# EEG-RM_040218P03.net
KiCad netlist of a schematic drawn in EAGLE
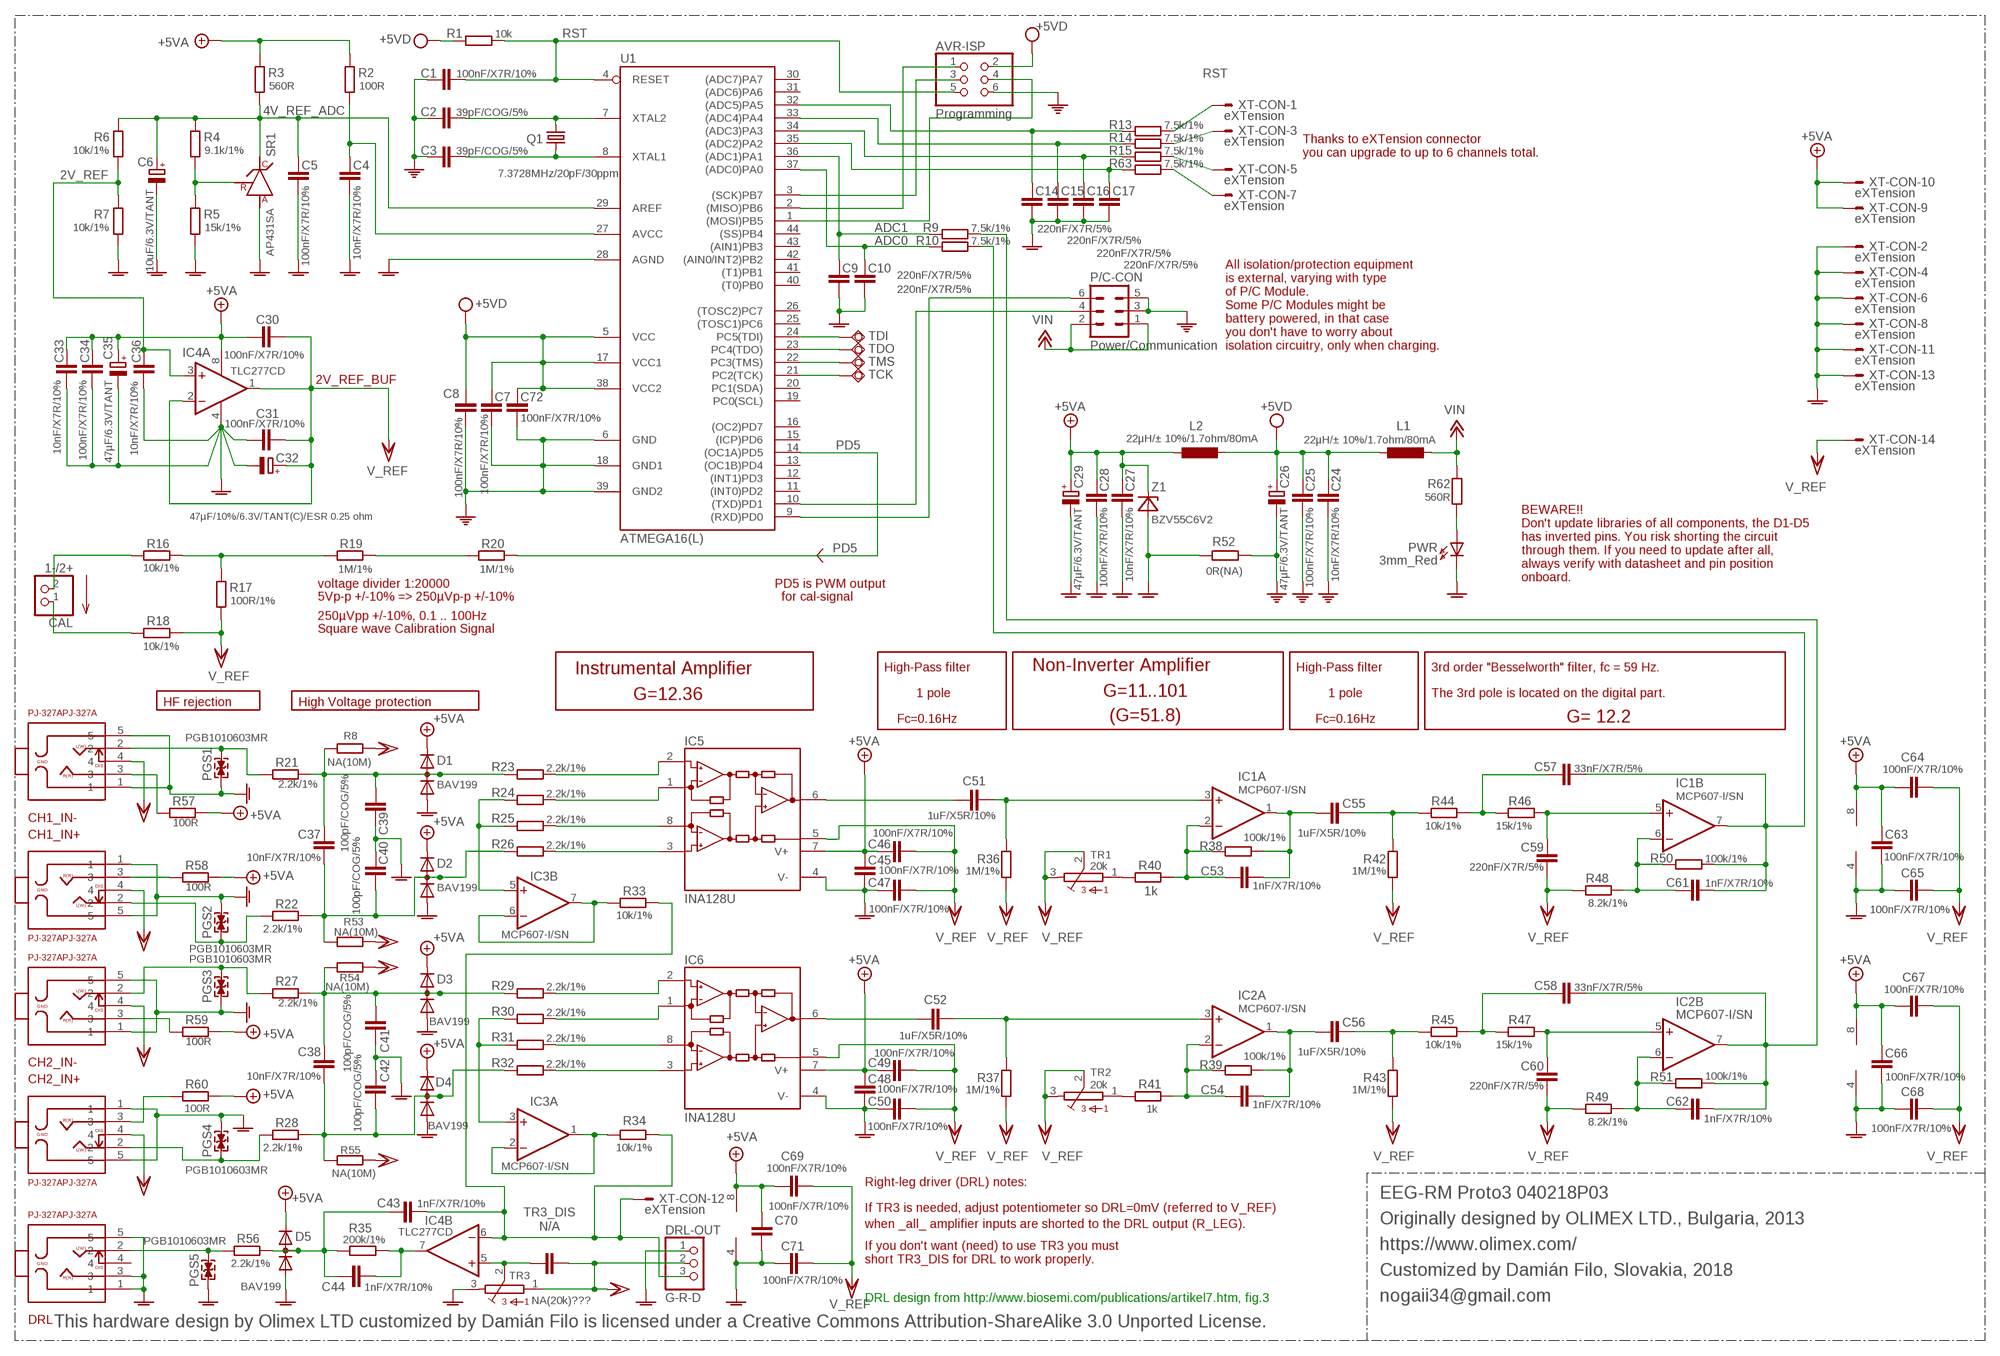
[diagram p0: schematic, sheet 1]

(export (version "E")
  (design (tool "Eeschema 10.0.6"))
  (components
    (comp (ref "AVR-ISP")
      (value "Programming")
      (footprint "eagle-import:2X03")
      (libsource (lib "eagle-import") (part "PINHD-2X3"))
    )
    (comp (ref "C1")
      (value "100nF/X7R/10%")
      (footprint "eagle-import:C0603")
      (libsource (lib "eagle-import") (part "C-EUC0603"))
    )
    (comp (ref "C2")
      (value "39pF/COG/5%")
      (footprint "eagle-import:C0603")
      (libsource (lib "eagle-import") (part "C-EUC0603"))
    )
    (comp (ref "C3")
      (value "39pF/COG/5%")
      (footprint "eagle-import:C0603")
      (libsource (lib "eagle-import") (part "C-EUC0603"))
    )
    (comp (ref "C4")
      (value "10nF/X7R/10%")
      (footprint "eagle-import:C0603")
      (libsource (lib "eagle-import") (part "C-EUC0603"))
    )
    (comp (ref "C5")
      (value "100nF/X7R/10%")
      (footprint "eagle-import:C0603")
      (libsource (lib "eagle-import") (part "C-EUC0603"))
    )
    (comp (ref "C6")
      (value "10uF/6.3V/TANT")
      (footprint "eagle-import:CT3216")
      (libsource (lib "eagle-import") (part "CPOL-EUCT3216"))
    )
    (comp (ref "C7")
      (value "100nF/X7R/10%")
      (footprint "eagle-import:C0603")
      (libsource (lib "eagle-import") (part "C-EUC0603"))
    )
    (comp (ref "C8")
      (value "100nF/X7R/10%")
      (footprint "eagle-import:C0603")
      (libsource (lib "eagle-import") (part "C-EUC0603"))
    )
    (comp (ref "C9")
      (value "220nF/X7R/5%")
      (footprint "eagle-import:C0603")
      (libsource (lib "eagle-import") (part "C-EUC0603"))
    )
    (comp (ref "C10")
      (value "220nF/X7R/5%")
      (footprint "eagle-import:C0603")
      (libsource (lib "eagle-import") (part "C-EUC0603"))
    )
    (comp (ref "C14")
      (value "220nF/X7R/5%")
      (footprint "eagle-import:C0603")
      (libsource (lib "eagle-import") (part "C-EUC0603"))
    )
    (comp (ref "C15")
      (value "220nF/X7R/5%")
      (footprint "eagle-import:C0603")
      (libsource (lib "eagle-import") (part "C-EUC0603"))
    )
    (comp (ref "C16")
      (value "220nF/X7R/5%")
      (footprint "eagle-import:C0603")
      (libsource (lib "eagle-import") (part "C-EUC0603"))
    )
    (comp (ref "C17")
      (value "220nF/X7R/5%")
      (footprint "eagle-import:C0603")
      (libsource (lib "eagle-import") (part "C-EUC0603"))
    )
    (comp (ref "C24")
      (value "10nF/X7R/10%")
      (footprint "eagle-import:C0603")
      (libsource (lib "eagle-import") (part "C-EUC0603"))
    )
    (comp (ref "C25")
      (value "100nF/X7R/10%")
      (footprint "eagle-import:C0603")
      (libsource (lib "eagle-import") (part "C-EUC0603"))
    )
    (comp (ref "C26")
      (value "47µF/6.3V/TANT")
      (footprint "eagle-import:CT3216")
      (libsource (lib "eagle-import") (part "CPOL-EUCT3216"))
    )
    (comp (ref "C27")
      (value "10nF/X7R/10%")
      (footprint "eagle-import:C0603")
      (libsource (lib "eagle-import") (part "C-EUC0603"))
    )
    (comp (ref "C28")
      (value "100nF/X7R/10%")
      (footprint "eagle-import:C0603")
      (libsource (lib "eagle-import") (part "C-EUC0603"))
    )
    (comp (ref "C29")
      (value "47µF/6.3V/TANT")
      (footprint "eagle-import:CT3216")
      (libsource (lib "eagle-import") (part "CPOL-EUCT3216"))
    )
    (comp (ref "C30")
      (value "100nF/X7R/10%")
      (footprint "eagle-import:C0603")
      (libsource (lib "eagle-import") (part "C-EUC0603"))
    )
    (comp (ref "C31")
      (value "100nF/X7R/10%")
      (footprint "eagle-import:C0603")
      (libsource (lib "eagle-import") (part "C-EUC0603"))
    )
    (comp (ref "C32")
      (value "47µF/10%/6.3V/TANT(C)/ESR 0.25 ohm")
      (footprint "eagle-import:CT3528")
      (libsource (lib "eagle-import") (part "CPOL-EUCT3528"))
    )
    (comp (ref "C33")
      (value "10nF/X7R/10%")
      (footprint "eagle-import:C0603")
      (libsource (lib "eagle-import") (part "C-EUC0603"))
    )
    (comp (ref "C34")
      (value "100nF/X7R/10%")
      (footprint "eagle-import:C0603")
      (libsource (lib "eagle-import") (part "C-EUC0603"))
    )
    (comp (ref "C35")
      (value "47µF/6.3V/TANT")
      (footprint "eagle-import:CT3216")
      (libsource (lib "eagle-import") (part "CPOL-EUCT3216"))
    )
    (comp (ref "C36")
      (value "10nF/X7R/10%")
      (footprint "eagle-import:C0603")
      (libsource (lib "eagle-import") (part "C-EUC0603"))
    )
    (comp (ref "C37")
      (value "10nF/X7R/10%")
      (footprint "eagle-import:C0603")
      (libsource (lib "eagle-import") (part "C-EUC0603"))
    )
    (comp (ref "C38")
      (value "10nF/X7R/10%")
      (footprint "eagle-import:C0603")
      (libsource (lib "eagle-import") (part "C-EUC0603"))
    )
    (comp (ref "C39")
      (value "100pF/COG/5%")
      (footprint "eagle-import:C0603")
      (libsource (lib "eagle-import") (part "C-EUC0603"))
    )
    (comp (ref "C40")
      (value "100pF/COG/5%")
      (footprint "eagle-import:C0603")
      (libsource (lib "eagle-import") (part "C-EUC0603"))
    )
    (comp (ref "C41")
      (value "100pF/COG/5%")
      (footprint "eagle-import:C0603")
      (libsource (lib "eagle-import") (part "C-EUC0603"))
    )
    (comp (ref "C42")
      (value "100pF/COG/5%")
      (footprint "eagle-import:C0603")
      (libsource (lib "eagle-import") (part "C-EUC0603"))
    )
    (comp (ref "C43")
      (value "1nF/X7R/10%")
      (footprint "eagle-import:C0603")
      (libsource (lib "eagle-import") (part "C-EUC0603"))
    )
    (comp (ref "C44")
      (value "1nF/X7R/10%")
      (footprint "eagle-import:C0603")
      (libsource (lib "eagle-import") (part "C-EUC0603"))
    )
    (comp (ref "C45")
      (value "100nF/X7R/10%")
      (footprint "eagle-import:C0603")
      (libsource (lib "eagle-import") (part "C-EUC0603"))
    )
    (comp (ref "C46")
      (value "100nF/X7R/10%")
      (footprint "eagle-import:C0603")
      (libsource (lib "eagle-import") (part "C-EUC0603"))
    )
    (comp (ref "C47")
      (value "100nF/X7R/10%")
      (footprint "eagle-import:C0603")
      (libsource (lib "eagle-import") (part "C-EUC0603"))
    )
    (comp (ref "C48")
      (value "100nF/X7R/10%")
      (footprint "eagle-import:C0603")
      (libsource (lib "eagle-import") (part "C-EUC0603"))
    )
    (comp (ref "C49")
      (value "100nF/X7R/10%")
      (footprint "eagle-import:C0603")
      (libsource (lib "eagle-import") (part "C-EUC0603"))
    )
    (comp (ref "C50")
      (value "100nF/X7R/10%")
      (footprint "eagle-import:C0603")
      (libsource (lib "eagle-import") (part "C-EUC0603"))
    )
    (comp (ref "C51")
      (value "1uF/X5R/10%")
      (footprint "eagle-import:C0603")
      (libsource (lib "eagle-import") (part "C-EUC0603"))
    )
    (comp (ref "C52")
      (value "1uF/X5R/10%")
      (footprint "eagle-import:C0603")
      (libsource (lib "eagle-import") (part "C-EUC0603"))
    )
    (comp (ref "C53")
      (value "1nF/X7R/10%")
      (footprint "eagle-import:C0603")
      (libsource (lib "eagle-import") (part "C-EUC0603"))
    )
    (comp (ref "C54")
      (value "1nF/X7R/10%")
      (footprint "eagle-import:C0603")
      (libsource (lib "eagle-import") (part "C-EUC0603"))
    )
    (comp (ref "C55")
      (value "1uF/X5R/10%")
      (footprint "eagle-import:C0603")
      (libsource (lib "eagle-import") (part "C-EUC0603"))
    )
    (comp (ref "C56")
      (value "1uF/X5R/10%")
      (footprint "eagle-import:C0603")
      (libsource (lib "eagle-import") (part "C-EUC0603"))
    )
    (comp (ref "C57")
      (value "33nF/X7R/5%")
      (footprint "eagle-import:C0603")
      (libsource (lib "eagle-import") (part "C-EUC0603"))
    )
    (comp (ref "C58")
      (value "33nF/X7R/5%")
      (footprint "eagle-import:C0603")
      (libsource (lib "eagle-import") (part "C-EUC0603"))
    )
    (comp (ref "C59")
      (value "220nF/X7R/5%")
      (footprint "eagle-import:C0603")
      (libsource (lib "eagle-import") (part "C-EUC0603"))
    )
    (comp (ref "C60")
      (value "220nF/X7R/5%")
      (footprint "eagle-import:C0603")
      (libsource (lib "eagle-import") (part "C-EUC0603"))
    )
    (comp (ref "C61")
      (value "1nF/X7R/10%")
      (footprint "eagle-import:C0603")
      (libsource (lib "eagle-import") (part "C-EUC0603"))
    )
    (comp (ref "C62")
      (value "1nF/X7R/10%")
      (footprint "eagle-import:C0603")
      (libsource (lib "eagle-import") (part "C-EUC0603"))
    )
    (comp (ref "C63")
      (value "100nF/X7R/10%")
      (footprint "eagle-import:C0603")
      (libsource (lib "eagle-import") (part "C-EUC0603"))
    )
    (comp (ref "C64")
      (value "100nF/X7R/10%")
      (footprint "eagle-import:C0603")
      (libsource (lib "eagle-import") (part "C-EUC0603"))
    )
    (comp (ref "C65")
      (value "100nF/X7R/10%")
      (footprint "eagle-import:C0603")
      (libsource (lib "eagle-import") (part "C-EUC0603"))
    )
    (comp (ref "C66")
      (value "100nF/X7R/10%")
      (footprint "eagle-import:C0603")
      (libsource (lib "eagle-import") (part "C-EUC0603"))
    )
    (comp (ref "C67")
      (value "100nF/X7R/10%")
      (footprint "eagle-import:C0603")
      (libsource (lib "eagle-import") (part "C-EUC0603"))
    )
    (comp (ref "C68")
      (value "100nF/X7R/10%")
      (footprint "eagle-import:C0603")
      (libsource (lib "eagle-import") (part "C-EUC0603"))
    )
    (comp (ref "C69")
      (value "100nF/X7R/10%")
      (footprint "eagle-import:C0603")
      (libsource (lib "eagle-import") (part "C-EUC0603"))
    )
    (comp (ref "C70")
      (value "100nF/X7R/10%")
      (footprint "eagle-import:C0603")
      (libsource (lib "eagle-import") (part "C-EUC0603"))
    )
    (comp (ref "C71")
      (value "100nF/X7R/10%")
      (footprint "eagle-import:C0603")
      (libsource (lib "eagle-import") (part "C-EUC0603"))
    )
    (comp (ref "C72")
      (value "100nF/X7R/10%")
      (footprint "eagle-import:C0603")
      (libsource (lib "eagle-import") (part "C-EUC0603"))
    )
    (comp (ref "CAL")
      (value "1-/2+")
      (footprint "eagle-import:1X02")
      (libsource (lib "eagle-import") (part "PINHD-1X2"))
    )
    (comp (ref "CH1_IN+")
      (value "PJ-327APJ-327A")
      (footprint "eagle-import:PJ-327A")
      (libsource (lib "eagle-import") (part "PJ-327APJ-327A"))
    )
    (comp (ref "CH1_IN-")
      (value "PJ-327APJ-327A")
      (footprint "eagle-import:PJ-327A")
      (libsource (lib "eagle-import") (part "PJ-327APJ-327A"))
    )
    (comp (ref "CH2_IN+")
      (value "PJ-327APJ-327A")
      (footprint "eagle-import:PJ-327A")
      (libsource (lib "eagle-import") (part "PJ-327APJ-327A"))
    )
    (comp (ref "CH2_IN-")
      (value "PJ-327APJ-327A")
      (footprint "eagle-import:PJ-327A")
      (libsource (lib "eagle-import") (part "PJ-327APJ-327A"))
    )
    (comp (ref "D1")
      (value "BAV199")
      (footprint "eagle-import:SOT23C")
      (libsource (lib "eagle-import") (part "DIODE_AC-AC__"))
    )
    (comp (ref "D2")
      (value "BAV199")
      (footprint "eagle-import:SOT23C")
      (libsource (lib "eagle-import") (part "DIODE_AC-AC__"))
    )
    (comp (ref "D3")
      (value "BAV199")
      (footprint "eagle-import:SOT23C")
      (libsource (lib "eagle-import") (part "DIODE_AC-AC__"))
    )
    (comp (ref "D4")
      (value "BAV199")
      (footprint "eagle-import:SOT23C")
      (libsource (lib "eagle-import") (part "DIODE_AC-AC__"))
    )
    (comp (ref "D5")
      (value "BAV199")
      (footprint "eagle-import:SOT23C")
      (libsource (lib "eagle-import") (part "DIODE_AC-AC__"))
    )
    (comp (ref "DRL")
      (value "PJ-327APJ-327A")
      (footprint "eagle-import:PJ-327A")
      (libsource (lib "eagle-import") (part "PJ-327APJ-327A"))
    )
    (comp (ref "DRL-OUT")
      (value "G-R-D")
      (footprint "eagle-import:1X03")
      (libsource (lib "eagle-import") (part "PINHD-1X3"))
    )
    (comp (ref "IC1")
      (value "MCP607-I/SN")
      (footprint "eagle-import:SO08")
      (libsource (lib "eagle-import") (part "LM358D"))
    )
    (comp (ref "IC2")
      (value "MCP607-I/SN")
      (footprint "eagle-import:SO08")
      (libsource (lib "eagle-import") (part "LM358D"))
    )
    (comp (ref "IC3")
      (value "MCP607-I/SN")
      (footprint "eagle-import:SO08")
      (libsource (lib "eagle-import") (part "LM358D"))
    )
    (comp (ref "IC4")
      (value "TLC277CD")
      (footprint "eagle-import:SO08")
      (libsource (lib "eagle-import") (part "LM358D"))
    )
    (comp (ref "IC5")
      (value "INA128U")
      (footprint "eagle-import:SO08")
      (fields (field (name "MF") "TEXAS INSTRUMENTS"))
      (libsource (lib "eagle-import") (part "INA128U"))
    )
    (comp (ref "IC6")
      (value "INA128U")
      (footprint "eagle-import:SO08")
      (fields (field (name "MF") "TEXAS INSTRUMENTS"))
      (libsource (lib "eagle-import") (part "INA128U"))
    )
    (comp (ref "L1")
      (value "22µH/± 10%/1.7ohm/80mA")
      (footprint "eagle-import:L2012C")
      (libsource (lib "eagle-import") (part "L-EUL2012C"))
    )
    (comp (ref "L2")
      (value "22µH/± 10%/1.7ohm/80mA")
      (footprint "eagle-import:L2012C")
      (libsource (lib "eagle-import") (part "L-EUL2012C"))
    )
    (comp (ref "P/C-CON")
      (value "Power/Communication")
      (footprint "eagle-import:ML6L")
      (libsource (lib "eagle-import") (part "ML6L"))
    )
    (comp (ref "PGS1")
      (value "PGB1010603MR")
      (footprint "eagle-import:0603")
      (libsource (lib "eagle-import") (part "PGB1010603MR(F2594TR-ND)"))
    )
    (comp (ref "PGS2")
      (value "PGB1010603MR")
      (footprint "eagle-import:0603")
      (libsource (lib "eagle-import") (part "PGB1010603MR(F2594TR-ND)"))
    )
    (comp (ref "PGS3")
      (value "PGB1010603MR")
      (footprint "eagle-import:0603")
      (libsource (lib "eagle-import") (part "PGB1010603MR(F2594TR-ND)"))
    )
    (comp (ref "PGS4")
      (value "PGB1010603MR")
      (footprint "eagle-import:0603")
      (libsource (lib "eagle-import") (part "PGB1010603MR(F2594TR-ND)"))
    )
    (comp (ref "PGS5")
      (value "PGB1010603MR")
      (footprint "eagle-import:0603")
      (libsource (lib "eagle-import") (part "PGB1010603MR(F2594TR-ND)"))
    )
    (comp (ref "PWR")
      (value "3mm_Red")
      (footprint "eagle-import:LED-3.0MM")
      (libsource (lib "eagle-import") (part "LED3.0MM"))
    )
    (comp (ref "Q1")
      (value "7.3728MHz/20pF/30ppm")
      (footprint "eagle-import:HC49_SMD2_THIN")
      (libsource (lib "eagle-import") (part "HC49/S1"))
    )
    (comp (ref "R1")
      (value "10k")
      (footprint "eagle-import:R0603")
      (libsource (lib "eagle-import") (part "R-EU_R0603"))
    )
    (comp (ref "R2")
      (value "100R")
      (footprint "eagle-import:R0603")
      (libsource (lib "eagle-import") (part "R-EU_R0603"))
    )
    (comp (ref "R3")
      (value "560R")
      (footprint "eagle-import:R0603")
      (libsource (lib "eagle-import") (part "R-EU_R0603"))
    )
    (comp (ref "R4")
      (value "9.1k/1%")
      (footprint "eagle-import:R0603")
      (libsource (lib "eagle-import") (part "R-EU_R0603"))
    )
    (comp (ref "R5")
      (value "15k/1%")
      (footprint "eagle-import:R0603")
      (libsource (lib "eagle-import") (part "R-EU_R0603"))
    )
    (comp (ref "R6")
      (value "10k/1%")
      (footprint "eagle-import:R0603")
      (libsource (lib "eagle-import") (part "R-EU_R0603"))
    )
    (comp (ref "R7")
      (value "10k/1%")
      (footprint "eagle-import:R0603")
      (libsource (lib "eagle-import") (part "R-EU_R0603"))
    )
    (comp (ref "R8")
      (value "NA(10M)")
      (footprint "eagle-import:R0603")
      (libsource (lib "eagle-import") (part "R-EU_R0603"))
    )
    (comp (ref "R9")
      (value "7.5k/1%")
      (footprint "eagle-import:M2012")
      (libsource (lib "eagle-import") (part "R-EU_M2012"))
    )
    (comp (ref "R10")
      (value "7.5k/1%")
      (footprint "eagle-import:M2012")
      (libsource (lib "eagle-import") (part "R-EU_M2012"))
    )
    (comp (ref "R13")
      (value "7.5k/1%")
      (footprint "eagle-import:M2012")
      (libsource (lib "eagle-import") (part "R-EU_M2012"))
    )
    (comp (ref "R14")
      (value "7.5k/1%")
      (footprint "eagle-import:M2012")
      (libsource (lib "eagle-import") (part "R-EU_M2012"))
    )
    (comp (ref "R15")
      (value "7.5k/1%")
      (footprint "eagle-import:M2012")
      (libsource (lib "eagle-import") (part "R-EU_M2012"))
    )
    (comp (ref "R16")
      (value "10k/1%")
      (footprint "eagle-import:R0603")
      (libsource (lib "eagle-import") (part "R-EU_R0603"))
    )
    (comp (ref "R17")
      (value "100R/1%")
      (footprint "eagle-import:R0603")
      (libsource (lib "eagle-import") (part "R-EU_R0603"))
    )
    (comp (ref "R18")
      (value "10k/1%")
      (footprint "eagle-import:R0603")
      (libsource (lib "eagle-import") (part "R-EU_R0603"))
    )
    (comp (ref "R19")
      (value "1M/1%")
      (footprint "eagle-import:R0603")
      (libsource (lib "eagle-import") (part "R-EU_R0603"))
    )
    (comp (ref "R20")
      (value "1M/1%")
      (footprint "eagle-import:R0603")
      (libsource (lib "eagle-import") (part "R-EU_R0603"))
    )
    (comp (ref "R21")
      (value "2.2k/1%")
      (footprint "eagle-import:R0603")
      (libsource (lib "eagle-import") (part "R-EU_R0603"))
    )
    (comp (ref "R22")
      (value "2.2k/1%")
      (footprint "eagle-import:R0603")
      (libsource (lib "eagle-import") (part "R-EU_R0603"))
    )
    (comp (ref "R23")
      (value "2.2k/1%")
      (footprint "eagle-import:R0603")
      (libsource (lib "eagle-import") (part "R-EU_R0603"))
    )
    (comp (ref "R24")
      (value "2.2k/1%")
      (footprint "eagle-import:R0603")
      (libsource (lib "eagle-import") (part "R-EU_R0603"))
    )
    (comp (ref "R25")
      (value "2.2k/1%")
      (footprint "eagle-import:R0603")
      (libsource (lib "eagle-import") (part "R-EU_R0603"))
    )
    (comp (ref "R26")
      (value "2.2k/1%")
      (footprint "eagle-import:R0603")
      (libsource (lib "eagle-import") (part "R-EU_R0603"))
    )
    (comp (ref "R27")
      (value "2.2k/1%")
      (footprint "eagle-import:R0603")
      (libsource (lib "eagle-import") (part "R-EU_R0603"))
    )
    (comp (ref "R28")
      (value "2.2k/1%")
      (footprint "eagle-import:R0603")
      (libsource (lib "eagle-import") (part "R-EU_R0603"))
    )
    (comp (ref "R29")
      (value "2.2k/1%")
      (footprint "eagle-import:R0603")
      (libsource (lib "eagle-import") (part "R-EU_R0603"))
    )
    (comp (ref "R30")
      (value "2.2k/1%")
      (footprint "eagle-import:R0603")
      (libsource (lib "eagle-import") (part "R-EU_R0603"))
    )
    (comp (ref "R31")
      (value "2.2k/1%")
      (footprint "eagle-import:R0603")
      (libsource (lib "eagle-import") (part "R-EU_R0603"))
    )
    (comp (ref "R32")
      (value "2.2k/1%")
      (footprint "eagle-import:R0603")
      (libsource (lib "eagle-import") (part "R-EU_R0603"))
    )
    (comp (ref "R33")
      (value "10k/1%")
      (footprint "eagle-import:R0603")
      (libsource (lib "eagle-import") (part "R-EU_R0603"))
    )
    (comp (ref "R34")
      (value "10k/1%")
      (footprint "eagle-import:R0603")
      (libsource (lib "eagle-import") (part "R-EU_R0603"))
    )
    (comp (ref "R35")
      (value "200k/1%")
      (footprint "eagle-import:R0603")
      (libsource (lib "eagle-import") (part "R-EU_R0603"))
    )
    (comp (ref "R36")
      (value "1M/1%")
      (footprint "eagle-import:R0603")
      (libsource (lib "eagle-import") (part "R-EU_R0603"))
    )
    (comp (ref "R37")
      (value "1M/1%")
      (footprint "eagle-import:R0603")
      (libsource (lib "eagle-import") (part "R-EU_R0603"))
    )
    (comp (ref "R38")
      (value "100k/1%")
      (footprint "eagle-import:R0603")
      (libsource (lib "eagle-import") (part "R-EU_R0603"))
    )
    (comp (ref "R39")
      (value "100k/1%")
      (footprint "eagle-import:R0603")
      (libsource (lib "eagle-import") (part "R-EU_R0603"))
    )
    (comp (ref "R40")
      (value "1k")
      (footprint "eagle-import:R0603")
      (libsource (lib "eagle-import") (part "R-EU_R0603"))
    )
    (comp (ref "R41")
      (value "1k")
      (footprint "eagle-import:R0603")
      (libsource (lib "eagle-import") (part "R-EU_R0603"))
    )
    (comp (ref "R42")
      (value "1M/1%")
      (footprint "eagle-import:R0603")
      (libsource (lib "eagle-import") (part "R-EU_R0603"))
    )
    (comp (ref "R43")
      (value "1M/1%")
      (footprint "eagle-import:R0603")
      (libsource (lib "eagle-import") (part "R-EU_R0603"))
    )
    (comp (ref "R44")
      (value "10k/1%")
      (footprint "eagle-import:R0603")
      (libsource (lib "eagle-import") (part "R-EU_R0603"))
    )
    (comp (ref "R45")
      (value "10k/1%")
      (footprint "eagle-import:R0603")
      (libsource (lib "eagle-import") (part "R-EU_R0603"))
    )
    (comp (ref "R46")
      (value "15k/1%")
      (footprint "eagle-import:R0603")
      (libsource (lib "eagle-import") (part "R-EU_R0603"))
    )
    (comp (ref "R47")
      (value "15k/1%")
      (footprint "eagle-import:R0603")
      (libsource (lib "eagle-import") (part "R-EU_R0603"))
    )
    (comp (ref "R48")
      (value "8.2k/1%")
      (footprint "eagle-import:R0603")
      (libsource (lib "eagle-import") (part "R-EU_R0603"))
    )
    (comp (ref "R49")
      (value "8.2k/1%")
      (footprint "eagle-import:R0603")
      (libsource (lib "eagle-import") (part "R-EU_R0603"))
    )
    (comp (ref "R50")
      (value "100k/1%")
      (footprint "eagle-import:R0603")
      (libsource (lib "eagle-import") (part "R-EU_R0603"))
    )
    (comp (ref "R51")
      (value "100k/1%")
      (footprint "eagle-import:R0603")
      (libsource (lib "eagle-import") (part "R-EU_R0603"))
    )
    (comp (ref "R52")
      (value "0R(NA)")
      (footprint "eagle-import:R0603")
      (libsource (lib "eagle-import") (part "R-EU_R0603"))
    )
    (comp (ref "R53")
      (value "NA(10M)")
      (footprint "eagle-import:R0603")
      (libsource (lib "eagle-import") (part "R-EU_R0603"))
    )
    (comp (ref "R54")
      (value "NA(10M)")
      (footprint "eagle-import:R0603")
      (libsource (lib "eagle-import") (part "R-EU_R0603"))
    )
    (comp (ref "R55")
      (value "NA(10M)")
      (footprint "eagle-import:R0603")
      (libsource (lib "eagle-import") (part "R-EU_R0603"))
    )
    (comp (ref "R56")
      (value "2.2k/1%")
      (footprint "eagle-import:R0603")
      (libsource (lib "eagle-import") (part "R-EU_R0603"))
    )
    (comp (ref "R57")
      (value "100R")
      (footprint "eagle-import:R0603")
      (libsource (lib "eagle-import") (part "R-EU_R0603"))
    )
    (comp (ref "R58")
      (value "100R")
      (footprint "eagle-import:R0603")
      (libsource (lib "eagle-import") (part "R-EU_R0603"))
    )
    (comp (ref "R59")
      (value "100R")
      (footprint "eagle-import:R0603")
      (libsource (lib "eagle-import") (part "R-EU_R0603"))
    )
    (comp (ref "R60")
      (value "100R")
      (footprint "eagle-import:R0603")
      (libsource (lib "eagle-import") (part "R-EU_R0603"))
    )
    (comp (ref "R62")
      (value "560R")
      (footprint "eagle-import:R0603")
      (libsource (lib "eagle-import") (part "R-EU_R0603"))
    )
    (comp (ref "R63")
      (value "7.5k/1%")
      (footprint "eagle-import:M2012")
      (libsource (lib "eagle-import") (part "R-EU_M2012"))
    )
    (comp (ref "SR1")
      (value "AP431SA")
      (footprint "eagle-import:SOT-23")
      (libsource (lib "eagle-import") (part "TL431'''"))
    )
    (comp (ref "TCK")
      (value "TESTPAD80/30")
      (footprint "eagle-import:SMD80_30")
      (libsource (lib "eagle-import") (part "TESTPAD80/30"))
    )
    (comp (ref "TDI")
      (value "TESTPAD80/30")
      (footprint "eagle-import:SMD80_30")
      (libsource (lib "eagle-import") (part "TESTPAD80/30"))
    )
    (comp (ref "TDO")
      (value "TESTPAD80/30")
      (footprint "eagle-import:SMD80_30")
      (libsource (lib "eagle-import") (part "TESTPAD80/30"))
    )
    (comp (ref "TMS")
      (value "TESTPAD80/30")
      (footprint "eagle-import:SMD80_30")
      (libsource (lib "eagle-import") (part "TESTPAD80/30"))
    )
    (comp (ref "TR1")
      (value "20k")
      (footprint "eagle-import:S64Y")
      (libsource (lib "eagle-import") (part "S64Y"))
    )
    (comp (ref "TR2")
      (value "20k")
      (footprint "eagle-import:S64Y")
      (libsource (lib "eagle-import") (part "S64Y"))
    )
    (comp (ref "TR3")
      (value "NA(20k)???")
      (footprint "eagle-import:S64Y")
      (libsource (lib "eagle-import") (part "S64Y"))
    )
    (comp (ref "TR3_DIS")
      (value "N/A")
      (footprint "eagle-import:C0402")
      (libsource (lib "eagle-import") (part "C-EUC0402"))
    )
    (comp (ref "U1")
      (value "ATMEGA16(L)")
      (footprint "eagle-import:44TQFP")
      (libsource (lib "eagle-import") (part "ATMEGA16"))
    )
    (comp (ref "XT-CON")
      (value "eXTension")
      (footprint "eagle-import:ML14L")
      (libsource (lib "eagle-import") (part "ML14EL"))
    )
    (comp (ref "Z1")
      (value "BZV55C6V2")
      (footprint "eagle-import:MINI-MELF")
      (libsource (lib "eagle-import") (part "ZDIOD-SMD"))
    )
  )
  (nets
    (net (code "1") (name "+5VA") (class "Default")
      (node (ref "C27") (pin "1") (pinfunction "1_1") (pintype "passive"))
      (node (ref "C28") (pin "1") (pinfunction "1_1") (pintype "passive"))
      (node (ref "C29") (pin "+") (pinfunction "+_+") (pintype "passive"))
      (node (ref "C30") (pin "2") (pinfunction "2_2") (pintype "passive"))
      (node (ref "C33") (pin "1") (pinfunction "1_1") (pintype "passive"))
      (node (ref "C34") (pin "1") (pinfunction "1_1") (pintype "passive"))
      (node (ref "C35") (pin "+") (pinfunction "+_+") (pintype "passive"))
      (node (ref "C45") (pin "1") (pinfunction "1_1") (pintype "passive"))
      (node (ref "C46") (pin "1") (pinfunction "1_1") (pintype "passive"))
      (node (ref "C48") (pin "1") (pinfunction "1_1") (pintype "passive"))
      (node (ref "C49") (pin "1") (pinfunction "1_1") (pintype "passive"))
      (node (ref "C63") (pin "1") (pinfunction "1_1") (pintype "passive"))
      (node (ref "C64") (pin "1") (pinfunction "1_1") (pintype "passive"))
      (node (ref "C66") (pin "1") (pinfunction "1_1") (pintype "passive"))
      (node (ref "C67") (pin "1") (pinfunction "1_1") (pintype "passive"))
      (node (ref "C69") (pin "1") (pinfunction "1_1") (pintype "passive"))
      (node (ref "C70") (pin "1") (pinfunction "1_1") (pintype "passive"))
      (node (ref "D1") (pin "1") (pinfunction "K_1") (pintype "passive"))
      (node (ref "D2") (pin "1") (pinfunction "K_1") (pintype "passive"))
      (node (ref "D3") (pin "1") (pinfunction "K_1") (pintype "passive"))
      (node (ref "D4") (pin "1") (pinfunction "K_1") (pintype "passive"))
      (node (ref "D5") (pin "1") (pinfunction "K_1") (pintype "passive"))
      (node (ref "IC1") (pin "8") (pinfunction "V+_8") (pintype "power_in"))
      (node (ref "IC2") (pin "8") (pinfunction "V+_8") (pintype "power_in"))
      (node (ref "IC3") (pin "8") (pinfunction "V+_8") (pintype "power_in"))
      (node (ref "IC4") (pin "8") (pinfunction "V+_8") (pintype "power_in"))
      (node (ref "IC5") (pin "7") (pinfunction "V+_7") (pintype "power_in"))
      (node (ref "IC6") (pin "7") (pinfunction "V+_7") (pintype "power_in"))
      (node (ref "L2") (pin "2") (pinfunction "2_2") (pintype "passive"))
      (node (ref "R2") (pin "2") (pinfunction "2_2") (pintype "passive"))
      (node (ref "R3") (pin "2") (pinfunction "2_2") (pintype "passive"))
      (node (ref "R57") (pin "2") (pinfunction "2_2") (pintype "passive"))
      (node (ref "R58") (pin "2") (pinfunction "2_2") (pintype "passive"))
      (node (ref "R59") (pin "2") (pinfunction "2_2") (pintype "passive"))
      (node (ref "R60") (pin "2") (pinfunction "2_2") (pintype "passive"))
      (node (ref "XT-CON") (pin "10") (pinfunction "S_10") (pintype "passive"))
      (node (ref "XT-CON") (pin "9") (pinfunction "S_9") (pintype "passive"))
      (node (ref "Z1") (pin "1") (pinfunction "C_1") (pintype "passive"))
    )
    (net (code "2") (name "+5VD") (class "Default")
      (node (ref "AVR-ISP") (pin "2") (pinfunction "2_2") (pintype "passive"))
      (node (ref "C24") (pin "1") (pinfunction "1_1") (pintype "passive"))
      (node (ref "C25") (pin "1") (pinfunction "1_1") (pintype "passive"))
      (node (ref "C26") (pin "+") (pinfunction "+_+") (pintype "passive"))
      (node (ref "C7") (pin "1") (pinfunction "1_1") (pintype "passive"))
      (node (ref "C72") (pin "1") (pinfunction "1_1") (pintype "passive"))
      (node (ref "C8") (pin "1") (pinfunction "1_1") (pintype "passive"))
      (node (ref "L1") (pin "2") (pinfunction "2_2") (pintype "passive"))
      (node (ref "L2") (pin "1") (pinfunction "1_1") (pintype "passive"))
      (node (ref "R1") (pin "1") (pinfunction "1_1") (pintype "passive"))
      (node (ref "U1") (pin "17") (pinfunction "VCC1_17") (pintype "bidirectional"))
      (node (ref "U1") (pin "38") (pinfunction "VCC2_38") (pintype "bidirectional"))
      (node (ref "U1") (pin "5") (pinfunction "VCC_5") (pintype "power_in"))
    )
    (net (code "3") (name "/2V_REF") (class "Default")
      (node (ref "C36") (pin "1") (pinfunction "1_1") (pintype "passive"))
      (node (ref "IC4") (pin "3") (pinfunction "+IN_3") (pintype "input"))
      (node (ref "R6") (pin "1") (pinfunction "1_1") (pintype "passive"))
      (node (ref "R7") (pin "2") (pinfunction "2_2") (pintype "passive"))
    )
    (net (code "4") (name "/4V_REF_ADC") (class "Default")
      (node (ref "C5") (pin "1") (pinfunction "1_1") (pintype "passive"))
      (node (ref "C6") (pin "+") (pinfunction "+_+") (pintype "passive"))
      (node (ref "R3") (pin "1") (pinfunction "1_1") (pintype "passive"))
      (node (ref "R4") (pin "2") (pinfunction "2_2") (pintype "passive"))
      (node (ref "R6") (pin "2") (pinfunction "2_2") (pintype "passive"))
      (node (ref "SR1") (pin "1") (pinfunction "C_1") (pintype "input"))
      (node (ref "U1") (pin "29") (pinfunction "AREF_29") (pintype "power_in"))
    )
    (net (code "5") (name "/ADC0") (class "Default")
      (node (ref "C10") (pin "1") (pinfunction "1_1") (pintype "passive"))
      (node (ref "R10") (pin "1") (pinfunction "1_1") (pintype "passive"))
      (node (ref "U1") (pin "37") (pinfunction "(ADC0)PA0_37") (pintype "bidirectional"))
    )
    (net (code "6") (name "/ADC1") (class "Default")
      (node (ref "C9") (pin "1") (pinfunction "1_1") (pintype "passive"))
      (node (ref "R9") (pin "1") (pinfunction "1_1") (pintype "passive"))
      (node (ref "U1") (pin "36") (pinfunction "(ADC1)PA1_36") (pintype "bidirectional"))
    )
    (net (code "7") (name "/PD5") (class "Default")
      (node (ref "R20") (pin "2") (pinfunction "2_2") (pintype "passive"))
      (node (ref "U1") (pin "14") (pinfunction "(OC1A)PD5_14") (pintype "bidirectional"))
    )
    (net (code "8") (name "/RST") (class "Default")
      (node (ref "AVR-ISP") (pin "5") (pinfunction "5_5") (pintype "passive"))
      (node (ref "C1") (pin "1") (pinfunction "1_1") (pintype "passive"))
      (node (ref "R1") (pin "2") (pinfunction "2_2") (pintype "passive"))
      (node (ref "U1") (pin "4") (pinfunction "RESET_4") (pintype "input"))
    )
    (net (code "9") (name "GNDA") (class "Default")
      (node (ref "C10") (pin "2") (pinfunction "2_2") (pintype "passive"))
      (node (ref "C14") (pin "2") (pinfunction "2_2") (pintype "passive"))
      (node (ref "C15") (pin "2") (pinfunction "2_2") (pintype "passive"))
      (node (ref "C16") (pin "2") (pinfunction "2_2") (pintype "passive"))
      (node (ref "C17") (pin "2") (pinfunction "2_2") (pintype "passive"))
      (node (ref "C27") (pin "2") (pinfunction "2_2") (pintype "passive"))
      (node (ref "C28") (pin "2") (pinfunction "2_2") (pintype "passive"))
      (node (ref "C29") (pin "-") (pinfunction "-_-") (pintype "passive"))
      (node (ref "C31") (pin "2") (pinfunction "2_2") (pintype "passive"))
      (node (ref "C32") (pin "-") (pinfunction "-_-") (pintype "passive"))
      (node (ref "C33") (pin "2") (pinfunction "2_2") (pintype "passive"))
      (node (ref "C34") (pin "2") (pinfunction "2_2") (pintype "passive"))
      (node (ref "C35") (pin "-") (pinfunction "-_-") (pintype "passive"))
      (node (ref "C36") (pin "2") (pinfunction "2_2") (pintype "passive"))
      (node (ref "C39") (pin "1") (pinfunction "1_1") (pintype "passive"))
      (node (ref "C4") (pin "2") (pinfunction "2_2") (pintype "passive"))
      (node (ref "C40") (pin "2") (pinfunction "2_2") (pintype "passive"))
      (node (ref "C41") (pin "1") (pinfunction "1_1") (pintype "passive"))
      (node (ref "C42") (pin "2") (pinfunction "2_2") (pintype "passive"))
      (node (ref "C45") (pin "2") (pinfunction "2_2") (pintype "passive"))
      (node (ref "C47") (pin "1") (pinfunction "1_1") (pintype "passive"))
      (node (ref "C48") (pin "2") (pinfunction "2_2") (pintype "passive"))
      (node (ref "C5") (pin "2") (pinfunction "2_2") (pintype "passive"))
      (node (ref "C50") (pin "1") (pinfunction "1_1") (pintype "passive"))
      (node (ref "C6") (pin "-") (pinfunction "-_-") (pintype "passive"))
      (node (ref "C63") (pin "2") (pinfunction "2_2") (pintype "passive"))
      (node (ref "C65") (pin "1") (pinfunction "1_1") (pintype "passive"))
      (node (ref "C66") (pin "2") (pinfunction "2_2") (pintype "passive"))
      (node (ref "C68") (pin "1") (pinfunction "1_1") (pintype "passive"))
      (node (ref "C70") (pin "2") (pinfunction "2_2") (pintype "passive"))
      (node (ref "C71") (pin "1") (pinfunction "1_1") (pintype "passive"))
      (node (ref "C9") (pin "2") (pinfunction "2_2") (pintype "passive"))
      (node (ref "CH1_IN+") (pin "1") (pinfunction "1_1") (pintype "bidirectional"))
      (node (ref "CH1_IN+") (pin "5") (pinfunction "5_5") (pintype "bidirectional"))
      (node (ref "CH1_IN-") (pin "1") (pinfunction "1_1") (pintype "bidirectional"))
      (node (ref "CH1_IN-") (pin "5") (pinfunction "5_5") (pintype "bidirectional"))
      (node (ref "CH2_IN+") (pin "1") (pinfunction "1_1") (pintype "bidirectional"))
      (node (ref "CH2_IN+") (pin "5") (pinfunction "5_5") (pintype "bidirectional"))
      (node (ref "CH2_IN-") (pin "1") (pinfunction "1_1") (pintype "bidirectional"))
      (node (ref "CH2_IN-") (pin "5") (pinfunction "5_5") (pintype "bidirectional"))
      (node (ref "D1") (pin "2") (pinfunction "A_2") (pintype "passive"))
      (node (ref "D2") (pin "2") (pinfunction "A_2") (pintype "passive"))
      (node (ref "D3") (pin "2") (pinfunction "A_2") (pintype "passive"))
      (node (ref "D4") (pin "2") (pinfunction "A_2") (pintype "passive"))
      (node (ref "D5") (pin "2") (pinfunction "A_2") (pintype "passive"))
      (node (ref "DRL") (pin "1") (pinfunction "1_1") (pintype "bidirectional"))
      (node (ref "DRL") (pin "3") (pinfunction "3_3") (pintype "bidirectional"))
      (node (ref "DRL") (pin "5") (pinfunction "5_5") (pintype "bidirectional"))
      (node (ref "DRL-OUT") (pin "1") (pinfunction "1_1") (pintype "passive"))
      (node (ref "IC1") (pin "4") (pinfunction "V-_4") (pintype "power_in"))
      (node (ref "IC2") (pin "4") (pinfunction "V-_4") (pintype "power_in"))
      (node (ref "IC3") (pin "4") (pinfunction "V-_4") (pintype "power_in"))
      (node (ref "IC4") (pin "4") (pinfunction "V-_4") (pintype "power_in"))
      (node (ref "IC5") (pin "4") (pinfunction "V-_4") (pintype "power_in"))
      (node (ref "IC6") (pin "4") (pinfunction "V-_4") (pintype "power_in"))
      (node (ref "PGS1") (pin "1") (pinfunction "1_1") (pintype "input"))
      (node (ref "PGS2") (pin "2") (pinfunction "2_2") (pintype "input"))
      (node (ref "PGS3") (pin "1") (pinfunction "1_1") (pintype "input"))
      (node (ref "PGS4") (pin "2") (pinfunction "2_2") (pintype "input"))
      (node (ref "PGS5") (pin "1") (pinfunction "1_1") (pintype "input"))
      (node (ref "PWR") (pin "K") (pinfunction "C_K") (pintype "passive"))
      (node (ref "R5") (pin "1") (pinfunction "1_1") (pintype "passive"))
      (node (ref "R52") (pin "1") (pinfunction "1_1") (pintype "passive"))
      (node (ref "R7") (pin "1") (pinfunction "1_1") (pintype "passive"))
      (node (ref "SR1") (pin "3") (pinfunction "A_3") (pintype "input"))
      (node (ref "TR3") (pin "3") (pinfunction "3_3") (pintype "passive"))
      (node (ref "U1") (pin "28") (pinfunction "AGND_28") (pintype "power_in"))
      (node (ref "XT-CON") (pin "11") (pinfunction "S_11") (pintype "passive"))
      (node (ref "XT-CON") (pin "13") (pinfunction "S_13") (pintype "passive"))
      (node (ref "XT-CON") (pin "2") (pinfunction "S_2") (pintype "passive"))
      (node (ref "XT-CON") (pin "4") (pinfunction "S_4") (pintype "passive"))
      (node (ref "XT-CON") (pin "6") (pinfunction "S_6") (pintype "passive"))
      (node (ref "XT-CON") (pin "8") (pinfunction "S_8") (pintype "passive"))
      (node (ref "Z1") (pin "2") (pinfunction "A_2") (pintype "passive"))
    )
    (net (code "10") (name "Net-(C55-Pad2)") (class "Default")
      (node (ref "C55") (pin "2") (pinfunction "2_2") (pintype "passive"))
      (node (ref "R42") (pin "1") (pinfunction "1_1") (pintype "passive"))
      (node (ref "R44") (pin "1") (pinfunction "1_1") (pintype "passive"))
    )
    (net (code "11") (name "Net-(C56-Pad2)") (class "Default")
      (node (ref "C56") (pin "2") (pinfunction "2_2") (pintype "passive"))
      (node (ref "R43") (pin "1") (pinfunction "1_1") (pintype "passive"))
      (node (ref "R45") (pin "1") (pinfunction "1_1") (pintype "passive"))
    )
    (net (code "12") (name "Net-(C57-Pad1)") (class "Default")
      (node (ref "C57") (pin "1") (pinfunction "1_1") (pintype "passive"))
      (node (ref "R44") (pin "2") (pinfunction "2_2") (pintype "passive"))
      (node (ref "R46") (pin "1") (pinfunction "1_1") (pintype "passive"))
    )
    (net (code "13") (name "Net-(C58-Pad1)") (class "Default")
      (node (ref "C58") (pin "1") (pinfunction "1_1") (pintype "passive"))
      (node (ref "R45") (pin "2") (pinfunction "2_2") (pintype "passive"))
      (node (ref "R47") (pin "1") (pinfunction "1_1") (pintype "passive"))
    )
    (net (code "14") (name "Net-(CAL-Pad1)") (class "Default")
      (node (ref "CAL") (pin "1") (pinfunction "1_1") (pintype "passive"))
      (node (ref "R18") (pin "1") (pinfunction "1_1") (pintype "passive"))
    )
    (net (code "15") (name "Net-(CAL-Pad2)") (class "Default")
      (node (ref "CAL") (pin "2") (pinfunction "2_2") (pintype "passive"))
      (node (ref "R16") (pin "1") (pinfunction "1_1") (pintype "passive"))
    )
    (net (code "16") (name "Net-(CH1_IN+-Pad2)") (class "Default")
      (node (ref "CH1_IN+") (pin "2") (pinfunction "2_2") (pintype "bidirectional"))
      (node (ref "PGS2") (pin "1") (pinfunction "1_1") (pintype "input"))
      (node (ref "R22") (pin "1") (pinfunction "1_1") (pintype "passive"))
    )
    (net (code "17") (name "Net-(CH1_IN+-Pad3)") (class "Default")
      (node (ref "CH1_IN+") (pin "3") (pinfunction "3_3") (pintype "bidirectional"))
      (node (ref "R58") (pin "1") (pinfunction "1_1") (pintype "passive"))
    )
    (net (code "18") (name "Net-(CH1_IN--Pad2)") (class "Default")
      (node (ref "CH1_IN-") (pin "2") (pinfunction "2_2") (pintype "bidirectional"))
      (node (ref "PGS1") (pin "2") (pinfunction "2_2") (pintype "input"))
      (node (ref "R21") (pin "1") (pinfunction "1_1") (pintype "passive"))
    )
    (net (code "19") (name "Net-(CH1_IN--Pad3)") (class "Default")
      (node (ref "CH1_IN-") (pin "3") (pinfunction "3_3") (pintype "bidirectional"))
      (node (ref "R57") (pin "1") (pinfunction "1_1") (pintype "passive"))
    )
    (net (code "20") (name "Net-(CH2_IN+-Pad2)") (class "Default")
      (node (ref "CH2_IN+") (pin "2") (pinfunction "2_2") (pintype "bidirectional"))
      (node (ref "PGS4") (pin "1") (pinfunction "1_1") (pintype "input"))
      (node (ref "R28") (pin "1") (pinfunction "1_1") (pintype "passive"))
    )
    (net (code "21") (name "Net-(CH2_IN+-Pad3)") (class "Default")
      (node (ref "CH2_IN+") (pin "3") (pinfunction "3_3") (pintype "bidirectional"))
      (node (ref "R60") (pin "1") (pinfunction "1_1") (pintype "passive"))
    )
    (net (code "22") (name "Net-(CH2_IN--Pad2)") (class "Default")
      (node (ref "CH2_IN-") (pin "2") (pinfunction "2_2") (pintype "bidirectional"))
      (node (ref "PGS3") (pin "2") (pinfunction "2_2") (pintype "input"))
      (node (ref "R27") (pin "1") (pinfunction "1_1") (pintype "passive"))
    )
    (net (code "23") (name "Net-(CH2_IN--Pad3)") (class "Default")
      (node (ref "CH2_IN-") (pin "3") (pinfunction "3_3") (pintype "bidirectional"))
      (node (ref "R59") (pin "1") (pinfunction "1_1") (pintype "passive"))
    )
    (net (code "24") (name "Net-(D1-AK)") (class "Default")
      (node (ref "C37") (pin "2") (pinfunction "2_2") (pintype "passive"))
      (node (ref "C39") (pin "2") (pinfunction "2_2") (pintype "passive"))
      (node (ref "D1") (pin "3") (pinfunction "AK_3") (pintype "passive"))
      (node (ref "R21") (pin "2") (pinfunction "2_2") (pintype "passive"))
      (node (ref "R23") (pin "2") (pinfunction "2_2") (pintype "passive"))
      (node (ref "R8") (pin "2") (pinfunction "2_2") (pintype "passive"))
    )
    (net (code "25") (name "Net-(D2-AK)") (class "Default")
      (node (ref "C37") (pin "1") (pinfunction "1_1") (pintype "passive"))
      (node (ref "C40") (pin "1") (pinfunction "1_1") (pintype "passive"))
      (node (ref "D2") (pin "3") (pinfunction "AK_3") (pintype "passive"))
      (node (ref "R22") (pin "2") (pinfunction "2_2") (pintype "passive"))
      (node (ref "R26") (pin "2") (pinfunction "2_2") (pintype "passive"))
      (node (ref "R53") (pin "2") (pinfunction "2_2") (pintype "passive"))
    )
    (net (code "26") (name "Net-(D3-AK)") (class "Default")
      (node (ref "C38") (pin "2") (pinfunction "2_2") (pintype "passive"))
      (node (ref "C41") (pin "2") (pinfunction "2_2") (pintype "passive"))
      (node (ref "D3") (pin "3") (pinfunction "AK_3") (pintype "passive"))
      (node (ref "R27") (pin "2") (pinfunction "2_2") (pintype "passive"))
      (node (ref "R29") (pin "2") (pinfunction "2_2") (pintype "passive"))
      (node (ref "R54") (pin "2") (pinfunction "2_2") (pintype "passive"))
    )
    (net (code "27") (name "Net-(D4-AK)") (class "Default")
      (node (ref "C38") (pin "1") (pinfunction "1_1") (pintype "passive"))
      (node (ref "C42") (pin "1") (pinfunction "1_1") (pintype "passive"))
      (node (ref "D4") (pin "3") (pinfunction "AK_3") (pintype "passive"))
      (node (ref "R28") (pin "2") (pinfunction "2_2") (pintype "passive"))
      (node (ref "R32") (pin "2") (pinfunction "2_2") (pintype "passive"))
      (node (ref "R55") (pin "2") (pinfunction "2_2") (pintype "passive"))
    )
    (net (code "28") (name "Net-(D5-AK)") (class "Default")
      (node (ref "C43") (pin "2") (pinfunction "2_2") (pintype "passive"))
      (node (ref "C44") (pin "2") (pinfunction "2_2") (pintype "passive"))
      (node (ref "D5") (pin "3") (pinfunction "AK_3") (pintype "passive"))
      (node (ref "R35") (pin "1") (pinfunction "1_1") (pintype "passive"))
      (node (ref "R56") (pin "2") (pinfunction "2_2") (pintype "passive"))
    )
    (net (code "29") (name "Net-(DRL-Pad2)") (class "Default")
      (node (ref "DRL") (pin "2") (pinfunction "2_2") (pintype "bidirectional"))
      (node (ref "PGS5") (pin "2") (pinfunction "2_2") (pintype "input"))
      (node (ref "R56") (pin "1") (pinfunction "1_1") (pintype "passive"))
    )
    (net (code "30") (name "Net-(IC1A-+IN)") (class "Default")
      (node (ref "C51") (pin "2") (pinfunction "2_2") (pintype "passive"))
      (node (ref "IC1") (pin "3") (pinfunction "+IN_3") (pintype "input"))
      (node (ref "R36") (pin "1") (pinfunction "1_1") (pintype "passive"))
    )
    (net (code "31") (name "Net-(IC1A--IN)") (class "Default")
      (node (ref "C53") (pin "1") (pinfunction "1_1") (pintype "passive"))
      (node (ref "IC1") (pin "2") (pinfunction "-IN_2") (pintype "input"))
      (node (ref "R38") (pin "1") (pinfunction "1_1") (pintype "passive"))
      (node (ref "R40") (pin "1") (pinfunction "1_1") (pintype "passive"))
    )
    (net (code "32") (name "Net-(IC1A-OUT)") (class "Default")
      (node (ref "C53") (pin "2") (pinfunction "2_2") (pintype "passive"))
      (node (ref "C55") (pin "1") (pinfunction "1_1") (pintype "passive"))
      (node (ref "IC1") (pin "1") (pinfunction "OUT_1") (pintype "output"))
      (node (ref "R38") (pin "2") (pinfunction "2_2") (pintype "passive"))
    )
    (net (code "33") (name "Net-(IC1B-+IN)") (class "Default")
      (node (ref "C59") (pin "1") (pinfunction "1_1") (pintype "passive"))
      (node (ref "IC1") (pin "5") (pinfunction "+IN_5") (pintype "input"))
      (node (ref "R46") (pin "2") (pinfunction "2_2") (pintype "passive"))
    )
    (net (code "34") (name "Net-(IC1B--IN)") (class "Default")
      (node (ref "C61") (pin "1") (pinfunction "1_1") (pintype "passive"))
      (node (ref "IC1") (pin "6") (pinfunction "-IN_6") (pintype "input"))
      (node (ref "R48") (pin "1") (pinfunction "1_1") (pintype "passive"))
      (node (ref "R50") (pin "1") (pinfunction "1_1") (pintype "passive"))
    )
    (net (code "35") (name "Net-(IC1B-OUT)") (class "Default")
      (node (ref "C57") (pin "2") (pinfunction "2_2") (pintype "passive"))
      (node (ref "C61") (pin "2") (pinfunction "2_2") (pintype "passive"))
      (node (ref "IC1") (pin "7") (pinfunction "OUT_7") (pintype "output"))
      (node (ref "R10") (pin "2") (pinfunction "2_2") (pintype "passive"))
      (node (ref "R50") (pin "2") (pinfunction "2_2") (pintype "passive"))
    )
    (net (code "36") (name "Net-(IC2A-+IN)") (class "Default")
      (node (ref "C52") (pin "2") (pinfunction "2_2") (pintype "passive"))
      (node (ref "IC2") (pin "3") (pinfunction "+IN_3") (pintype "input"))
      (node (ref "R37") (pin "1") (pinfunction "1_1") (pintype "passive"))
    )
    (net (code "37") (name "Net-(IC2A--IN)") (class "Default")
      (node (ref "C54") (pin "1") (pinfunction "1_1") (pintype "passive"))
      (node (ref "IC2") (pin "2") (pinfunction "-IN_2") (pintype "input"))
      (node (ref "R39") (pin "1") (pinfunction "1_1") (pintype "passive"))
      (node (ref "R41") (pin "1") (pinfunction "1_1") (pintype "passive"))
    )
    (net (code "38") (name "Net-(IC2A-OUT)") (class "Default")
      (node (ref "C54") (pin "2") (pinfunction "2_2") (pintype "passive"))
      (node (ref "C56") (pin "1") (pinfunction "1_1") (pintype "passive"))
      (node (ref "IC2") (pin "1") (pinfunction "OUT_1") (pintype "output"))
      (node (ref "R39") (pin "2") (pinfunction "2_2") (pintype "passive"))
    )
    (net (code "39") (name "Net-(IC2B-+IN)") (class "Default")
      (node (ref "C60") (pin "1") (pinfunction "1_1") (pintype "passive"))
      (node (ref "IC2") (pin "5") (pinfunction "+IN_5") (pintype "input"))
      (node (ref "R47") (pin "2") (pinfunction "2_2") (pintype "passive"))
    )
    (net (code "40") (name "Net-(IC2B--IN)") (class "Default")
      (node (ref "C62") (pin "1") (pinfunction "1_1") (pintype "passive"))
      (node (ref "IC2") (pin "6") (pinfunction "-IN_6") (pintype "input"))
      (node (ref "R49") (pin "1") (pinfunction "1_1") (pintype "passive"))
      (node (ref "R51") (pin "1") (pinfunction "1_1") (pintype "passive"))
    )
    (net (code "41") (name "Net-(IC2B-OUT)") (class "Default")
      (node (ref "C58") (pin "2") (pinfunction "2_2") (pintype "passive"))
      (node (ref "C62") (pin "2") (pinfunction "2_2") (pintype "passive"))
      (node (ref "IC2") (pin "7") (pinfunction "OUT_7") (pintype "output"))
      (node (ref "R51") (pin "2") (pinfunction "2_2") (pintype "passive"))
      (node (ref "R9") (pin "2") (pinfunction "2_2") (pintype "passive"))
    )
    (net (code "42") (name "Net-(IC3A-+IN)") (class "Default")
      (node (ref "IC3") (pin "3") (pinfunction "+IN_3") (pintype "input"))
      (node (ref "R30") (pin "2") (pinfunction "2_2") (pintype "passive"))
      (node (ref "R31") (pin "2") (pinfunction "2_2") (pintype "passive"))
    )
    (net (code "43") (name "Net-(IC3A--IN)") (class "Default")
      (node (ref "IC3") (pin "1") (pinfunction "OUT_1") (pintype "output"))
      (node (ref "IC3") (pin "2") (pinfunction "-IN_2") (pintype "input"))
      (node (ref "R34") (pin "2") (pinfunction "2_2") (pintype "passive"))
    )
    (net (code "44") (name "Net-(IC3B-+IN)") (class "Default")
      (node (ref "IC3") (pin "5") (pinfunction "+IN_5") (pintype "input"))
      (node (ref "R24") (pin "2") (pinfunction "2_2") (pintype "passive"))
      (node (ref "R25") (pin "2") (pinfunction "2_2") (pintype "passive"))
    )
    (net (code "45") (name "Net-(IC3B--IN)") (class "Default")
      (node (ref "IC3") (pin "6") (pinfunction "-IN_6") (pintype "input"))
      (node (ref "IC3") (pin "7") (pinfunction "OUT_7") (pintype "output"))
      (node (ref "R33") (pin "2") (pinfunction "2_2") (pintype "passive"))
    )
    (net (code "46") (name "Net-(IC4B-+IN)") (class "Default")
      (node (ref "IC4") (pin "5") (pinfunction "+IN_5") (pintype "input"))
      (node (ref "TR3") (pin "2") (pinfunction "2_2") (pintype "passive"))
      (node (ref "TR3_DIS") (pin "1") (pinfunction "1_1") (pintype "passive"))
    )
    (net (code "47") (name "Net-(IC4B--IN)") (class "Default")
      (node (ref "C43") (pin "1") (pinfunction "1_1") (pintype "passive"))
      (node (ref "DRL-OUT") (pin "3") (pinfunction "3_3") (pintype "passive"))
      (node (ref "IC4") (pin "6") (pinfunction "-IN_6") (pintype "input"))
      (node (ref "R33") (pin "1") (pinfunction "1_1") (pintype "passive"))
      (node (ref "R34") (pin "1") (pinfunction "1_1") (pintype "passive"))
      (node (ref "XT-CON") (pin "12") (pinfunction "S_12") (pintype "passive"))
    )
    (net (code "48") (name "Net-(IC4B-OUT)") (class "Default")
      (node (ref "C44") (pin "1") (pinfunction "1_1") (pintype "passive"))
      (node (ref "IC4") (pin "7") (pinfunction "OUT_7") (pintype "output"))
      (node (ref "R35") (pin "2") (pinfunction "2_2") (pintype "passive"))
    )
    (net (code "49") (name "Net-(IC5-+IN)") (class "Default")
      (node (ref "IC5") (pin "3") (pinfunction "+IN_3") (pintype "input"))
      (node (ref "R26") (pin "1") (pinfunction "1_1") (pintype "passive"))
    )
    (net (code "50") (name "Net-(IC5--IN)") (class "Default")
      (node (ref "IC5") (pin "2") (pinfunction "-IN_2") (pintype "input"))
      (node (ref "R23") (pin "1") (pinfunction "1_1") (pintype "passive"))
    )
    (net (code "51") (name "Net-(IC5-OUT)") (class "Default")
      (node (ref "C51") (pin "1") (pinfunction "1_1") (pintype "passive"))
      (node (ref "IC5") (pin "6") (pinfunction "OUT_6") (pintype "output"))
    )
    (net (code "52") (name "Net-(IC5-RG-Pad1)") (class "Default")
      (node (ref "IC5") (pin "1") (pinfunction "RG_1") (pintype "passive"))
      (node (ref "R24") (pin "1") (pinfunction "1_1") (pintype "passive"))
    )
    (net (code "53") (name "Net-(IC5-RG-Pad8)") (class "Default")
      (node (ref "IC5") (pin "8") (pinfunction "RG_8") (pintype "passive"))
      (node (ref "R25") (pin "1") (pinfunction "1_1") (pintype "passive"))
    )
    (net (code "54") (name "Net-(IC6-+IN)") (class "Default")
      (node (ref "IC6") (pin "3") (pinfunction "+IN_3") (pintype "input"))
      (node (ref "R32") (pin "1") (pinfunction "1_1") (pintype "passive"))
    )
    (net (code "55") (name "Net-(IC6--IN)") (class "Default")
      (node (ref "IC6") (pin "2") (pinfunction "-IN_2") (pintype "input"))
      (node (ref "R29") (pin "1") (pinfunction "1_1") (pintype "passive"))
    )
    (net (code "56") (name "Net-(IC6-OUT)") (class "Default")
      (node (ref "C52") (pin "1") (pinfunction "1_1") (pintype "passive"))
      (node (ref "IC6") (pin "6") (pinfunction "OUT_6") (pintype "output"))
    )
    (net (code "57") (name "Net-(IC6-RG-Pad1)") (class "Default")
      (node (ref "IC6") (pin "1") (pinfunction "RG_1") (pintype "passive"))
      (node (ref "R30") (pin "1") (pinfunction "1_1") (pintype "passive"))
    )
    (net (code "58") (name "Net-(IC6-RG-Pad8)") (class "Default")
      (node (ref "IC6") (pin "8") (pinfunction "RG_8") (pintype "passive"))
      (node (ref "R31") (pin "1") (pinfunction "1_1") (pintype "passive"))
    )
    (net (code "59") (name "Net-(PWR-PadA)") (class "Default")
      (node (ref "PWR") (pin "A") (pinfunction "A_A") (pintype "passive"))
      (node (ref "R62") (pin "1") (pinfunction "1_1") (pintype "passive"))
    )
    (net (code "60") (name "Net-(R16-Pad2)") (class "Default")
      (node (ref "R16") (pin "2") (pinfunction "2_2") (pintype "passive"))
      (node (ref "R17") (pin "2") (pinfunction "2_2") (pintype "passive"))
      (node (ref "R19") (pin "1") (pinfunction "1_1") (pintype "passive"))
    )
    (net (code "61") (name "Net-(R19-Pad2)") (class "Default")
      (node (ref "R19") (pin "2") (pinfunction "2_2") (pintype "passive"))
      (node (ref "R20") (pin "1") (pinfunction "1_1") (pintype "passive"))
    )
    (net (code "62") (name "Net-(R40-Pad2)") (class "Default")
      (node (ref "R40") (pin "2") (pinfunction "2_2") (pintype "passive"))
      (node (ref "TR1") (pin "1") (pinfunction "1_1") (pintype "passive"))
    )
    (net (code "63") (name "Net-(R41-Pad2)") (class "Default")
      (node (ref "R41") (pin "2") (pinfunction "2_2") (pintype "passive"))
      (node (ref "TR2") (pin "1") (pinfunction "1_1") (pintype "passive"))
    )
    (net (code "64") (name "Net-(SR1-R)") (class "Default")
      (node (ref "R4") (pin "1") (pinfunction "1_1") (pintype "passive"))
      (node (ref "R5") (pin "2") (pinfunction "2_2") (pintype "passive"))
      (node (ref "SR1") (pin "2") (pinfunction "R_2") (pintype "input"))
    )
    (net (code "65") (name "Net-(TCK-PP)") (class "Default")
      (node (ref "TCK") (pin "P$1") (pinfunction "PP_P$1") (pintype "passive"))
      (node (ref "U1") (pin "21") (pinfunction "PC2(TCK)_21") (pintype "bidirectional"))
    )
    (net (code "66") (name "Net-(TDI-PP)") (class "Default")
      (node (ref "TDI") (pin "P$1") (pinfunction "PP_P$1") (pintype "passive"))
      (node (ref "U1") (pin "24") (pinfunction "PC5(TDI)_24") (pintype "bidirectional"))
    )
    (net (code "67") (name "Net-(TDO-PP)") (class "Default")
      (node (ref "TDO") (pin "P$1") (pinfunction "PP_P$1") (pintype "passive"))
      (node (ref "U1") (pin "23") (pinfunction "PC4(TDO)_23") (pintype "bidirectional"))
    )
    (net (code "68") (name "Net-(TMS-PP)") (class "Default")
      (node (ref "TMS") (pin "P$1") (pinfunction "PP_P$1") (pintype "passive"))
      (node (ref "U1") (pin "22") (pinfunction "PC3(TMS)_22") (pintype "bidirectional"))
    )
    (net (code "69") (name "Net-(U1-(ADC2)PA2)") (class "Default")
      (node (ref "C17") (pin "1") (pinfunction "1_1") (pintype "passive"))
      (node (ref "R63") (pin "1") (pinfunction "1_1") (pintype "passive"))
      (node (ref "U1") (pin "35") (pinfunction "(ADC2)PA2_35") (pintype "bidirectional"))
    )
    (net (code "70") (name "Net-(U1-(ADC3)PA3)") (class "Default")
      (node (ref "C16") (pin "1") (pinfunction "1_1") (pintype "passive"))
      (node (ref "R15") (pin "1") (pinfunction "1_1") (pintype "passive"))
      (node (ref "U1") (pin "34") (pinfunction "(ADC3)PA3_34") (pintype "bidirectional"))
    )
    (net (code "71") (name "Net-(U1-(ADC4)PA4)") (class "Default")
      (node (ref "C15") (pin "1") (pinfunction "1_1") (pintype "passive"))
      (node (ref "R14") (pin "1") (pinfunction "1_1") (pintype "passive"))
      (node (ref "U1") (pin "33") (pinfunction "(ADC4)PA4_33") (pintype "bidirectional"))
    )
    (net (code "72") (name "Net-(U1-(ADC5)PA5)") (class "Default")
      (node (ref "C14") (pin "1") (pinfunction "1_1") (pintype "passive"))
      (node (ref "R13") (pin "1") (pinfunction "1_1") (pintype "passive"))
      (node (ref "U1") (pin "32") (pinfunction "(ADC5)PA5_32") (pintype "bidirectional"))
    )
    (net (code "73") (name "Net-(U1-(MISO)PB6)") (class "Default")
      (node (ref "AVR-ISP") (pin "1") (pinfunction "1_1") (pintype "passive"))
      (node (ref "U1") (pin "2") (pinfunction "(MISO)PB6_2") (pintype "bidirectional"))
    )
    (net (code "74") (name "Net-(U1-(MOSI)PB5)") (class "Default")
      (node (ref "AVR-ISP") (pin "4") (pinfunction "4_4") (pintype "passive"))
      (node (ref "U1") (pin "1") (pinfunction "(MOSI)PB5_1") (pintype "bidirectional"))
    )
    (net (code "75") (name "Net-(U1-(RXD)PD0)") (class "Default")
      (node (ref "P/C-CON") (pin "6") (pinfunction "6_6") (pintype "passive"))
      (node (ref "U1") (pin "9") (pinfunction "(RXD)PD0_9") (pintype "bidirectional"))
    )
    (net (code "76") (name "Net-(U1-(SCK)PB7)") (class "Default")
      (node (ref "AVR-ISP") (pin "3") (pinfunction "3_3") (pintype "passive"))
      (node (ref "U1") (pin "3") (pinfunction "(SCK)PB7_3") (pintype "bidirectional"))
    )
    (net (code "77") (name "Net-(U1-(TXD)PD1)") (class "Default")
      (node (ref "P/C-CON") (pin "4") (pinfunction "4_4") (pintype "passive"))
      (node (ref "U1") (pin "10") (pinfunction "(TXD)PD1_10") (pintype "bidirectional"))
    )
    (net (code "78") (name "Net-(U1-AVCC)") (class "Default")
      (node (ref "C4") (pin "1") (pinfunction "1_1") (pintype "passive"))
      (node (ref "R2") (pin "1") (pinfunction "1_1") (pintype "passive"))
      (node (ref "U1") (pin "27") (pinfunction "AVCC_27") (pintype "power_in"))
    )
    (net (code "79") (name "Net-(U1-XTAL1)") (class "Default")
      (node (ref "C3") (pin "1") (pinfunction "1_1") (pintype "passive"))
      (node (ref "Q1") (pin "2") (pinfunction "2_2") (pintype "passive"))
      (node (ref "U1") (pin "8") (pinfunction "XTAL1_8") (pintype "bidirectional"))
    )
    (net (code "80") (name "Net-(U1-XTAL2)") (class "Default")
      (node (ref "C2") (pin "1") (pinfunction "1_1") (pintype "passive"))
      (node (ref "Q1") (pin "1") (pinfunction "1_1") (pintype "passive"))
      (node (ref "U1") (pin "7") (pinfunction "XTAL2_7") (pintype "bidirectional"))
    )
    (net (code "81") (name "Net-(XT-CONA-S)") (class "Default")
      (node (ref "R13") (pin "2") (pinfunction "2_2") (pintype "passive"))
      (node (ref "XT-CON") (pin "1") (pinfunction "S_1") (pintype "passive"))
    )
    (net (code "82") (name "Net-(XT-CONH-S)") (class "Default")
      (node (ref "R14") (pin "2") (pinfunction "2_2") (pintype "passive"))
      (node (ref "XT-CON") (pin "3") (pinfunction "S_3") (pintype "passive"))
    )
    (net (code "83") (name "Net-(XT-CONJ-S)") (class "Default")
      (node (ref "R15") (pin "2") (pinfunction "2_2") (pintype "passive"))
      (node (ref "XT-CON") (pin "5") (pinfunction "S_5") (pintype "passive"))
    )
    (net (code "84") (name "Net-(XT-CONL-S)") (class "Default")
      (node (ref "R63") (pin "2") (pinfunction "2_2") (pintype "passive"))
      (node (ref "XT-CON") (pin "7") (pinfunction "S_7") (pintype "passive"))
    )
    (net (code "85") (name "PE") (class "Default")
      (node (ref "AVR-ISP") (pin "6") (pinfunction "6_6") (pintype "passive"))
      (node (ref "C1") (pin "2") (pinfunction "2_2") (pintype "passive"))
      (node (ref "C2") (pin "2") (pinfunction "2_2") (pintype "passive"))
      (node (ref "C24") (pin "2") (pinfunction "2_2") (pintype "passive"))
      (node (ref "C25") (pin "2") (pinfunction "2_2") (pintype "passive"))
      (node (ref "C26") (pin "-") (pinfunction "-_-") (pintype "passive"))
      (node (ref "C3") (pin "2") (pinfunction "2_2") (pintype "passive"))
      (node (ref "C7") (pin "2") (pinfunction "2_2") (pintype "passive"))
      (node (ref "C72") (pin "2") (pinfunction "2_2") (pintype "passive"))
      (node (ref "C8") (pin "2") (pinfunction "2_2") (pintype "passive"))
      (node (ref "P/C-CON") (pin "3") (pinfunction "3_3") (pintype "passive"))
      (node (ref "P/C-CON") (pin "5") (pinfunction "5_5") (pintype "passive"))
      (node (ref "R52") (pin "2") (pinfunction "2_2") (pintype "passive"))
      (node (ref "U1") (pin "18") (pinfunction "GND1_18") (pintype "bidirectional"))
      (node (ref "U1") (pin "39") (pinfunction "GND2_39") (pintype "bidirectional"))
      (node (ref "U1") (pin "6") (pinfunction "GND_6") (pintype "power_in"))
    )
    (net (code "86") (name "VIN") (class "Default")
      (node (ref "L1") (pin "1") (pinfunction "1_1") (pintype "passive"))
      (node (ref "P/C-CON") (pin "1") (pinfunction "1_1") (pintype "passive"))
      (node (ref "P/C-CON") (pin "2") (pinfunction "2_2") (pintype "passive"))
      (node (ref "R62") (pin "2") (pinfunction "2_2") (pintype "passive"))
    )
    (net (code "87") (name "V_REF") (class "Default")
      (node (ref "C30") (pin "1") (pinfunction "1_1") (pintype "passive"))
      (node (ref "C31") (pin "1") (pinfunction "1_1") (pintype "passive"))
      (node (ref "C32") (pin "+") (pinfunction "+_+") (pintype "passive"))
      (node (ref "C46") (pin "2") (pinfunction "2_2") (pintype "passive"))
      (node (ref "C47") (pin "2") (pinfunction "2_2") (pintype "passive"))
      (node (ref "C49") (pin "2") (pinfunction "2_2") (pintype "passive"))
      (node (ref "C50") (pin "2") (pinfunction "2_2") (pintype "passive"))
      (node (ref "C59") (pin "2") (pinfunction "2_2") (pintype "passive"))
      (node (ref "C60") (pin "2") (pinfunction "2_2") (pintype "passive"))
      (node (ref "C64") (pin "2") (pinfunction "2_2") (pintype "passive"))
      (node (ref "C65") (pin "2") (pinfunction "2_2") (pintype "passive"))
      (node (ref "C67") (pin "2") (pinfunction "2_2") (pintype "passive"))
      (node (ref "C68") (pin "2") (pinfunction "2_2") (pintype "passive"))
      (node (ref "C69") (pin "2") (pinfunction "2_2") (pintype "passive"))
      (node (ref "C71") (pin "2") (pinfunction "2_2") (pintype "passive"))
      (node (ref "CH1_IN+") (pin "4") (pinfunction "4_4") (pintype "bidirectional"))
      (node (ref "CH1_IN-") (pin "4") (pinfunction "4_4") (pintype "bidirectional"))
      (node (ref "CH2_IN+") (pin "4") (pinfunction "4_4") (pintype "bidirectional"))
      (node (ref "CH2_IN-") (pin "4") (pinfunction "4_4") (pintype "bidirectional"))
      (node (ref "DRL-OUT") (pin "2") (pinfunction "2_2") (pintype "passive"))
      (node (ref "IC4") (pin "1") (pinfunction "OUT_1") (pintype "output"))
      (node (ref "IC4") (pin "2") (pinfunction "-IN_2") (pintype "input"))
      (node (ref "IC5") (pin "5") (pinfunction "REF_5") (pintype "passive"))
      (node (ref "IC6") (pin "5") (pinfunction "REF_5") (pintype "passive"))
      (node (ref "R17") (pin "1") (pinfunction "1_1") (pintype "passive"))
      (node (ref "R18") (pin "2") (pinfunction "2_2") (pintype "passive"))
      (node (ref "R36") (pin "2") (pinfunction "2_2") (pintype "passive"))
      (node (ref "R37") (pin "2") (pinfunction "2_2") (pintype "passive"))
      (node (ref "R42") (pin "2") (pinfunction "2_2") (pintype "passive"))
      (node (ref "R43") (pin "2") (pinfunction "2_2") (pintype "passive"))
      (node (ref "R48") (pin "2") (pinfunction "2_2") (pintype "passive"))
      (node (ref "R49") (pin "2") (pinfunction "2_2") (pintype "passive"))
      (node (ref "R53") (pin "1") (pinfunction "1_1") (pintype "passive"))
      (node (ref "R54") (pin "1") (pinfunction "1_1") (pintype "passive"))
      (node (ref "R55") (pin "1") (pinfunction "1_1") (pintype "passive"))
      (node (ref "R8") (pin "1") (pinfunction "1_1") (pintype "passive"))
      (node (ref "TR1") (pin "2") (pinfunction "2_2") (pintype "passive"))
      (node (ref "TR1") (pin "3") (pinfunction "3_3") (pintype "passive"))
      (node (ref "TR2") (pin "2") (pinfunction "2_2") (pintype "passive"))
      (node (ref "TR2") (pin "3") (pinfunction "3_3") (pintype "passive"))
      (node (ref "TR3") (pin "1") (pinfunction "1_1") (pintype "passive"))
      (node (ref "TR3_DIS") (pin "2") (pinfunction "2_2") (pintype "passive"))
      (node (ref "XT-CON") (pin "14") (pinfunction "S_14") (pintype "passive"))
    )
    (net (code "88") (name "unconnected-(DRL-Pad4)") (class "Default")
      (node (ref "DRL") (pin "4") (pinfunction "4_4") (pintype "bidirectional"))
    )
    (net (code "89") (name "unconnected-(U1-(ADC6)PA6-Pad31)") (class "Default")
      (node (ref "U1") (pin "31") (pinfunction "(ADC6)PA6_31") (pintype "bidirectional"))
    )
    (net (code "90") (name "unconnected-(U1-(ADC7)PA7-Pad30)") (class "Default")
      (node (ref "U1") (pin "30") (pinfunction "(ADC7)PA7_30") (pintype "bidirectional"))
    )
    (net (code "91") (name "unconnected-(U1-(AIN0{slash}INT2)PB2-Pad42)") (class "Default")
      (node (ref "U1") (pin "42") (pinfunction "(AIN0/INT2)PB2_42") (pintype "bidirectional"))
    )
    (net (code "92") (name "unconnected-(U1-(AIN1)PB3-Pad43)") (class "Default")
      (node (ref "U1") (pin "43") (pinfunction "(AIN1)PB3_43") (pintype "bidirectional"))
    )
    (net (code "93") (name "unconnected-(U1-(ICP)PD6-Pad15)") (class "Default")
      (node (ref "U1") (pin "15") (pinfunction "(ICP)PD6_15") (pintype "bidirectional"))
    )
    (net (code "94") (name "unconnected-(U1-(INT0)PD2-Pad11)") (class "Default")
      (node (ref "U1") (pin "11") (pinfunction "(INT0)PD2_11") (pintype "bidirectional"))
    )
    (net (code "95") (name "unconnected-(U1-(INT1)PD3-Pad12)") (class "Default")
      (node (ref "U1") (pin "12") (pinfunction "(INT1)PD3_12") (pintype "bidirectional"))
    )
    (net (code "96") (name "unconnected-(U1-(OC1B)PD4-Pad13)") (class "Default")
      (node (ref "U1") (pin "13") (pinfunction "(OC1B)PD4_13") (pintype "bidirectional"))
    )
    (net (code "97") (name "unconnected-(U1-(OC2)PD7-Pad16)") (class "Default")
      (node (ref "U1") (pin "16") (pinfunction "(OC2)PD7_16") (pintype "bidirectional"))
    )
    (net (code "98") (name "unconnected-(U1-(SS)PB4-Pad44)") (class "Default")
      (node (ref "U1") (pin "44") (pinfunction "(SS)PB4_44") (pintype "bidirectional"))
    )
    (net (code "99") (name "unconnected-(U1-(T0)PB0-Pad40)") (class "Default")
      (node (ref "U1") (pin "40") (pinfunction "(T0)PB0_40") (pintype "bidirectional"))
    )
    (net (code "100") (name "unconnected-(U1-(T1)PB1-Pad41)") (class "Default")
      (node (ref "U1") (pin "41") (pinfunction "(T1)PB1_41") (pintype "bidirectional"))
    )
    (net (code "101") (name "unconnected-(U1-(TOSC1)PC6-Pad25)") (class "Default")
      (node (ref "U1") (pin "25") (pinfunction "(TOSC1)PC6_25") (pintype "bidirectional"))
    )
    (net (code "102") (name "unconnected-(U1-(TOSC2)PC7-Pad26)") (class "Default")
      (node (ref "U1") (pin "26") (pinfunction "(TOSC2)PC7_26") (pintype "bidirectional"))
    )
    (net (code "103") (name "unconnected-(U1-PC0(SCL)-Pad19)") (class "Default")
      (node (ref "U1") (pin "19") (pinfunction "PC0(SCL)_19") (pintype "bidirectional"))
    )
    (net (code "104") (name "unconnected-(U1-PC1(SDA)-Pad20)") (class "Default")
      (node (ref "U1") (pin "20") (pinfunction "PC1(SDA)_20") (pintype "bidirectional"))
    )
  )
)
